# CH9343-_USB_V0_0_1.net
KiCad netlist of a schematic drawn in Altium Designer
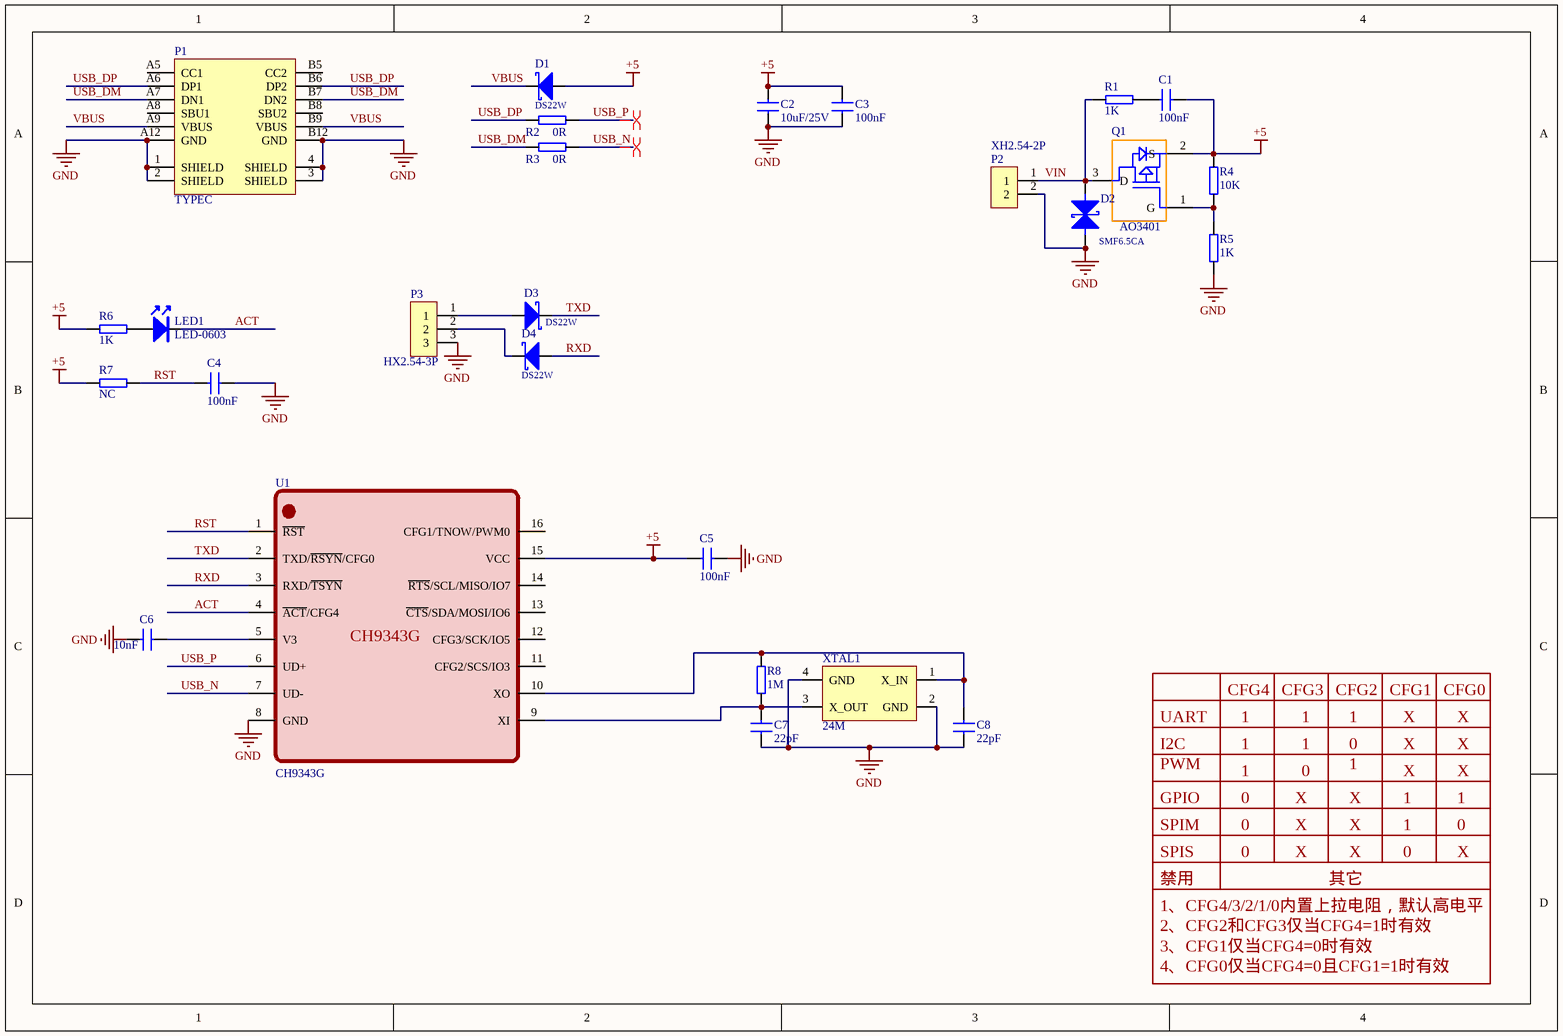
[diagram p0: CH9343-安卓USB转串口板V0.0.1版本.SchDoc]

(export (version "E")
  (design (tool "Eeschema 10.0.6"))
  (components
    (comp (ref "C1")
      (value "100nF")
      (footprint "C-0603")
      (description "陶瓷电容，50V/X7R/10%")
      (libsource (lib "PassiveComponent") (part "CAP_0603"))
    )
    (comp (ref "C2")
      (value "10uF/25V")
      (footprint "C-0805")
      (description "X5R/25V/10%")
      (libsource (lib "PassiveComponent") (part "CAP_0805"))
    )
    (comp (ref "C3")
      (value "100nF")
      (footprint "C-0603")
      (description "X7R/50V/10%")
      (libsource (lib "PassiveComponent") (part "CAP_0603"))
    )
    (comp (ref "C4")
      (value "100nF")
      (footprint "C-0603")
      (description "X7R/50V/10%")
      (libsource (lib "PassiveComponent") (part "CAP_0603"))
    )
    (comp (ref "C5")
      (value "100nF")
      (footprint "C-0603")
      (description "X7R/50V/10%")
      (libsource (lib "PassiveComponent") (part "CAP_0603"))
    )
    (comp (ref "C6")
      (value "10nF")
      (footprint "C-0603")
      (description "X7R/50V/10%")
      (libsource (lib "PassiveComponent") (part "CAP_0603"))
    )
    (comp (ref "C7")
      (value "22pF")
      (footprint "C-0603")
      (description "50V/COG/10%")
      (libsource (lib "PassiveComponent") (part "CAP_0603"))
    )
    (comp (ref "C8")
      (value "22pF")
      (footprint "C-0603")
      (description "50V/COG/10%")
      (libsource (lib "PassiveComponent") (part "CAP_0603"))
    )
    (comp (ref "D1")
      (value "DS22W")
      (footprint "SOD-123F")
      (description "肖特基二极管")
      (libsource (lib "PassiveComponent") (part "D-SCHOTKY"))
    )
    (comp (ref "D2")
      (value "SMF6.5CA")
      (footprint "DO-SOD-123FL_L2.8-W1.8-LS3.7-BI")
      (description "双向瞬变二极管")
      (libsource (lib "PassiveComponent") (part "TVS"))
    )
    (comp (ref "D3")
      (value "DS22W")
      (footprint "SOD-123F")
      (description "肖特基二极管")
      (libsource (lib "PassiveComponent") (part "D-SCHOTKY"))
    )
    (comp (ref "D4")
      (value "DS22W")
      (footprint "SOD-123F")
      (description "肖特基二极管")
      (libsource (lib "PassiveComponent") (part "D-SCHOTKY"))
    )
    (comp (ref "LED1")
      (value "LED-0603")
      (footprint "LED-0603")
      (description "发光二极管")
      (libsource (lib "PassiveComponent") (part "LED-0603"))
    )
    (comp (ref "P1")
      (value "TYPEC")
      (footprint "Type c-16p")
      (libsource (lib "Connetctor") (part "Type c 16p"))
    )
    (comp (ref "P2")
      (value "XH2.54-2P")
      (footprint "XH2.54-2P")
      (description "直针")
      (libsource (lib "Connetctor") (part "XH2.54-2P"))
    )
    (comp (ref "P3")
      (value "HX2.54-3P")
      (footprint "XH2.54-3P")
      (description "XH2.54-3P 直针 座")
      (libsource (lib "Connetctor") (part "XH2.54-3P"))
    )
    (comp (ref "Q1")
      (value "AO3401")
      (footprint "SOT-23")
      (description "P沟道")
      (libsource (lib "PassiveComponent") (part "MOSFET P"))
    )
    (comp (ref "R1")
      (value "1K")
      (footprint "R-0603")
      (description "5% ,1/10W")
      (libsource (lib "PassiveComponent") (part "R-0603"))
    )
    (comp (ref "R2") (value "0R") (footprint "R-0603") (libsource (lib "PassiveComponent") (part "R-0603")))
    (comp (ref "R3") (value "0R") (footprint "R-0603") (libsource (lib "PassiveComponent") (part "R-0603")))
    (comp (ref "R4")
      (value "10K")
      (footprint "R-0603")
      (description "5% ,1/10W")
      (libsource (lib "PassiveComponent") (part "R-0603"))
    )
    (comp (ref "R5")
      (value "1K")
      (footprint "R-0603")
      (description "5% ,1/10W")
      (libsource (lib "PassiveComponent") (part "R-0603"))
    )
    (comp (ref "R6")
      (value "1K")
      (footprint "R-0603")
      (description "贴片电阻，5%")
      (libsource (lib "PassiveComponent") (part "R-0603"))
    )
    (comp (ref "R7")
      (value "NC")
      (footprint "R-0603")
      (description "贴片电阻，5%")
      (libsource (lib "PassiveComponent") (part "R-0603"))
    )
    (comp (ref "R8")
      (value "1M")
      (footprint "R-0603")
      (description "5% ,1/10W")
      (libsource (lib "PassiveComponent") (part "R-0603"))
    )
    (comp (ref "U1")
      (value "CH9343G")
      (footprint "SO-16")
      (description "安卓USB转串口，SO-16")
      (libsource (lib "Component") (part "CH9343G"))
    )
    (comp (ref "XTAL1")
      (value "24M")
      (footprint "XTAL-3225")
      (description "贴片无源晶振")
      (libsource (lib "PassiveComponent") (part "XTAL-3225"))
    )
  )
  (nets
    (net (code "1") (name "+5") (class "Default")
      (node (ref "C1") (pin "2") (pinfunction "2_2") (pintype "passive"))
      (node (ref "C2") (pin "1") (pinfunction "1_1") (pintype "passive"))
      (node (ref "C3") (pin "2") (pinfunction "2_2") (pintype "passive"))
      (node (ref "C5") (pin "1") (pinfunction "1_1") (pintype "passive"))
      (node (ref "D1") (pin "1") (pinfunction "1_1") (pintype "passive"))
      (node (ref "Q1") (pin "2") (pinfunction "S_2") (pintype "passive"))
      (node (ref "R4") (pin "2") (pinfunction "2_2") (pintype "passive"))
      (node (ref "R6") (pin "2") (pinfunction "2_2") (pintype "passive"))
      (node (ref "R7") (pin "2") (pinfunction "2_2") (pintype "passive"))
      (node (ref "U1") (pin "15") (pinfunction "VCC_15") (pintype "passive"))
    )
    (net (code "2") (name "/ACT") (class "Default")
      (node (ref "LED1") (pin "2") (pinfunction "2_2") (pintype "passive"))
      (node (ref "U1") (pin "4") (pinfunction "~{ACT}/CFG4_4") (pintype "passive"))
    )
    (net (code "3") (name "/RST") (class "Default")
      (node (ref "C4") (pin "1") (pinfunction "1_1") (pintype "passive"))
      (node (ref "R7") (pin "1") (pinfunction "1_1") (pintype "passive"))
      (node (ref "U1") (pin "1") (pinfunction "~{RST}_1") (pintype "passive"))
    )
    (net (code "4") (name "/RXD") (class "Default")
      (node (ref "D4") (pin "1") (pinfunction "1_1") (pintype "passive"))
      (node (ref "U1") (pin "3") (pinfunction "RXD/~{TSYN}_3") (pintype "passive"))
    )
    (net (code "5") (name "/TXD") (class "Default")
      (node (ref "D3") (pin "2") (pinfunction "2_2") (pintype "passive"))
      (node (ref "U1") (pin "2") (pinfunction "TXD/~{RSYN}/CFG0_2") (pintype "passive"))
    )
    (net (code "6") (name "/USB_DM") (class "Default")
      (node (ref "P1") (pin "A7") (pinfunction "DN1_A7") (pintype "passive"))
      (node (ref "P1") (pin "B7") (pinfunction "DN2_B7") (pintype "passive"))
      (node (ref "R3") (pin "1") (pinfunction "1_1") (pintype "passive"))
    )
    (net (code "7") (name "/USB_DP") (class "Default")
      (node (ref "P1") (pin "A6") (pinfunction "DP1_A6") (pintype "passive"))
      (node (ref "P1") (pin "B6") (pinfunction "DP2_B6") (pintype "passive"))
      (node (ref "R2") (pin "1") (pinfunction "1_1") (pintype "passive"))
    )
    (net (code "8") (name "/USB_N") (class "Default")
      (node (ref "R3") (pin "2") (pinfunction "2_2") (pintype "passive"))
      (node (ref "U1") (pin "7") (pinfunction "UD-_7") (pintype "passive"))
    )
    (net (code "9") (name "/USB_P") (class "Default")
      (node (ref "R2") (pin "2") (pinfunction "2_2") (pintype "passive"))
      (node (ref "U1") (pin "6") (pinfunction "UD+_6") (pintype "passive"))
    )
    (net (code "10") (name "/VBUS") (class "Default")
      (node (ref "D1") (pin "2") (pinfunction "2_2") (pintype "passive"))
      (node (ref "P1") (pin "A9") (pinfunction "VBUS_A9") (pintype "passive"))
      (node (ref "P1") (pin "B9") (pinfunction "VBUS_B9") (pintype "passive"))
    )
    (net (code "11") (name "/VIN") (class "Default")
      (node (ref "D2") (pin "1") (pinfunction "1_1") (pintype "passive"))
      (node (ref "P2") (pin "1") (pinfunction "1_1") (pintype "passive"))
      (node (ref "Q1") (pin "3") (pinfunction "D_3") (pintype "passive"))
      (node (ref "R1") (pin "2") (pinfunction "2_2") (pintype "passive"))
    )
    (net (code "12") (name "GND") (class "Default")
      (node (ref "C2") (pin "2") (pinfunction "2_2") (pintype "passive"))
      (node (ref "C3") (pin "1") (pinfunction "1_1") (pintype "passive"))
      (node (ref "C4") (pin "2") (pinfunction "2_2") (pintype "passive"))
      (node (ref "C5") (pin "2") (pinfunction "2_2") (pintype "passive"))
      (node (ref "C6") (pin "1") (pinfunction "1_1") (pintype "passive"))
      (node (ref "C7") (pin "1") (pinfunction "1_1") (pintype "passive"))
      (node (ref "C8") (pin "2") (pinfunction "2_2") (pintype "passive"))
      (node (ref "D2") (pin "2") (pinfunction "2_2") (pintype "passive"))
      (node (ref "P1") (pin "1") (pinfunction "SHIELD_1") (pintype "passive"))
      (node (ref "P1") (pin "2") (pinfunction "SHIELD_2") (pintype "passive"))
      (node (ref "P1") (pin "3") (pinfunction "SHIELD_3") (pintype "passive"))
      (node (ref "P1") (pin "4") (pinfunction "SHIELD_4") (pintype "passive"))
      (node (ref "P1") (pin "A12") (pinfunction "GND_A12") (pintype "passive"))
      (node (ref "P1") (pin "B12") (pinfunction "GND_B12") (pintype "passive"))
      (node (ref "P2") (pin "2") (pinfunction "2_2") (pintype "passive"))
      (node (ref "P3") (pin "3") (pinfunction "3_3") (pintype "passive"))
      (node (ref "R5") (pin "1") (pinfunction "1_1") (pintype "passive"))
      (node (ref "U1") (pin "8") (pinfunction "GND_8") (pintype "passive"))
      (node (ref "XTAL1") (pin "2") (pinfunction "GND_2") (pintype "passive"))
      (node (ref "XTAL1") (pin "4") (pinfunction "GND_4") (pintype "passive"))
    )
    (net (code "13") (name "Net-(C1-Pad1)") (class "Default")
      (node (ref "C1") (pin "1") (pinfunction "1_1") (pintype "passive"))
      (node (ref "R1") (pin "1") (pinfunction "1_1") (pintype "passive"))
    )
    (net (code "14") (name "Net-(D3-Pad1)") (class "Default")
      (node (ref "D3") (pin "1") (pinfunction "1_1") (pintype "passive"))
      (node (ref "P3") (pin "1") (pinfunction "1_1") (pintype "passive"))
    )
    (net (code "15") (name "Net-(D4-Pad2)") (class "Default")
      (node (ref "D4") (pin "2") (pinfunction "2_2") (pintype "passive"))
      (node (ref "P3") (pin "2") (pinfunction "2_2") (pintype "passive"))
    )
    (net (code "16") (name "Net-(LED1-Pad1)") (class "Default")
      (node (ref "LED1") (pin "1") (pinfunction "1_1") (pintype "passive"))
      (node (ref "R6") (pin "1") (pinfunction "1_1") (pintype "passive"))
    )
    (net (code "17") (name "Net-(Q1-G)") (class "Default")
      (node (ref "Q1") (pin "1") (pinfunction "G_1") (pintype "passive"))
      (node (ref "R4") (pin "1") (pinfunction "1_1") (pintype "passive"))
      (node (ref "R5") (pin "2") (pinfunction "2_2") (pintype "passive"))
    )
    (net (code "18") (name "Net-(U1-V3)") (class "Default")
      (node (ref "C6") (pin "2") (pinfunction "2_2") (pintype "passive"))
      (node (ref "U1") (pin "5") (pinfunction "V3_5") (pintype "passive"))
    )
    (net (code "19") (name "Net-(U1-XI)") (class "Default")
      (node (ref "C7") (pin "2") (pinfunction "2_2") (pintype "passive"))
      (node (ref "R8") (pin "2") (pinfunction "2_2") (pintype "passive"))
      (node (ref "U1") (pin "9") (pinfunction "XI_9") (pintype "passive"))
      (node (ref "XTAL1") (pin "3") (pinfunction "X_OUT_3") (pintype "passive"))
    )
    (net (code "20") (name "Net-(U1-XO)") (class "Default")
      (node (ref "C8") (pin "1") (pinfunction "1_1") (pintype "passive"))
      (node (ref "R8") (pin "1") (pinfunction "1_1") (pintype "passive"))
      (node (ref "U1") (pin "10") (pinfunction "XO_10") (pintype "passive"))
      (node (ref "XTAL1") (pin "1") (pinfunction "X_IN_1") (pintype "passive"))
    )
    (net (code "21") (name "unconnected-(P1-CC1-PadA5)") (class "Default")
      (node (ref "P1") (pin "A5") (pinfunction "CC1_A5") (pintype "passive"))
    )
    (net (code "22") (name "unconnected-(P1-CC2-PadB5)") (class "Default")
      (node (ref "P1") (pin "B5") (pinfunction "CC2_B5") (pintype "passive"))
    )
    (net (code "23") (name "unconnected-(P1-SBU1-PadA8)") (class "Default")
      (node (ref "P1") (pin "A8") (pinfunction "SBU1_A8") (pintype "passive"))
    )
    (net (code "24") (name "unconnected-(P1-SBU2-PadB8)") (class "Default")
      (node (ref "P1") (pin "B8") (pinfunction "SBU2_B8") (pintype "passive"))
    )
    (net (code "25") (name "unconnected-(U1-CFG1{slash}TNOW{slash}PWM0-Pad16)") (class "Default")
      (node (ref "U1") (pin "16") (pinfunction "CFG1/TNOW/PWM0_16") (pintype "passive"))
    )
    (net (code "26") (name "unconnected-(U1-CFG2{slash}SCS{slash}IO3-Pad11)") (class "Default")
      (node (ref "U1") (pin "11") (pinfunction "CFG2/SCS/IO3_11") (pintype "passive"))
    )
    (net (code "27") (name "unconnected-(U1-CFG3{slash}SCK{slash}IO5-Pad12)") (class "Default")
      (node (ref "U1") (pin "12") (pinfunction "CFG3/SCK/IO5_12") (pintype "passive"))
    )
    (net (code "28") (name "unconnected-(U1-~{CTS}{slash}SDA{slash}MOSI{slash}IO6-Pad13)") (class "Default")
      (node (ref "U1") (pin "13") (pinfunction "~{CTS}/SDA/MOSI/IO6_13") (pintype "passive"))
    )
    (net (code "29") (name "unconnected-(U1-~{RTS}{slash}SCL{slash}MISO{slash}IO7-Pad14)") (class "Default")
      (node (ref "U1") (pin "14") (pinfunction "~{RTS}/SCL/MISO/IO7_14") (pintype "passive"))
    )
  )
)
